# ATmega4809_Curiosity_Nano_Target_MCU.net
KiCad netlist of a schematic drawn in Altium Designer
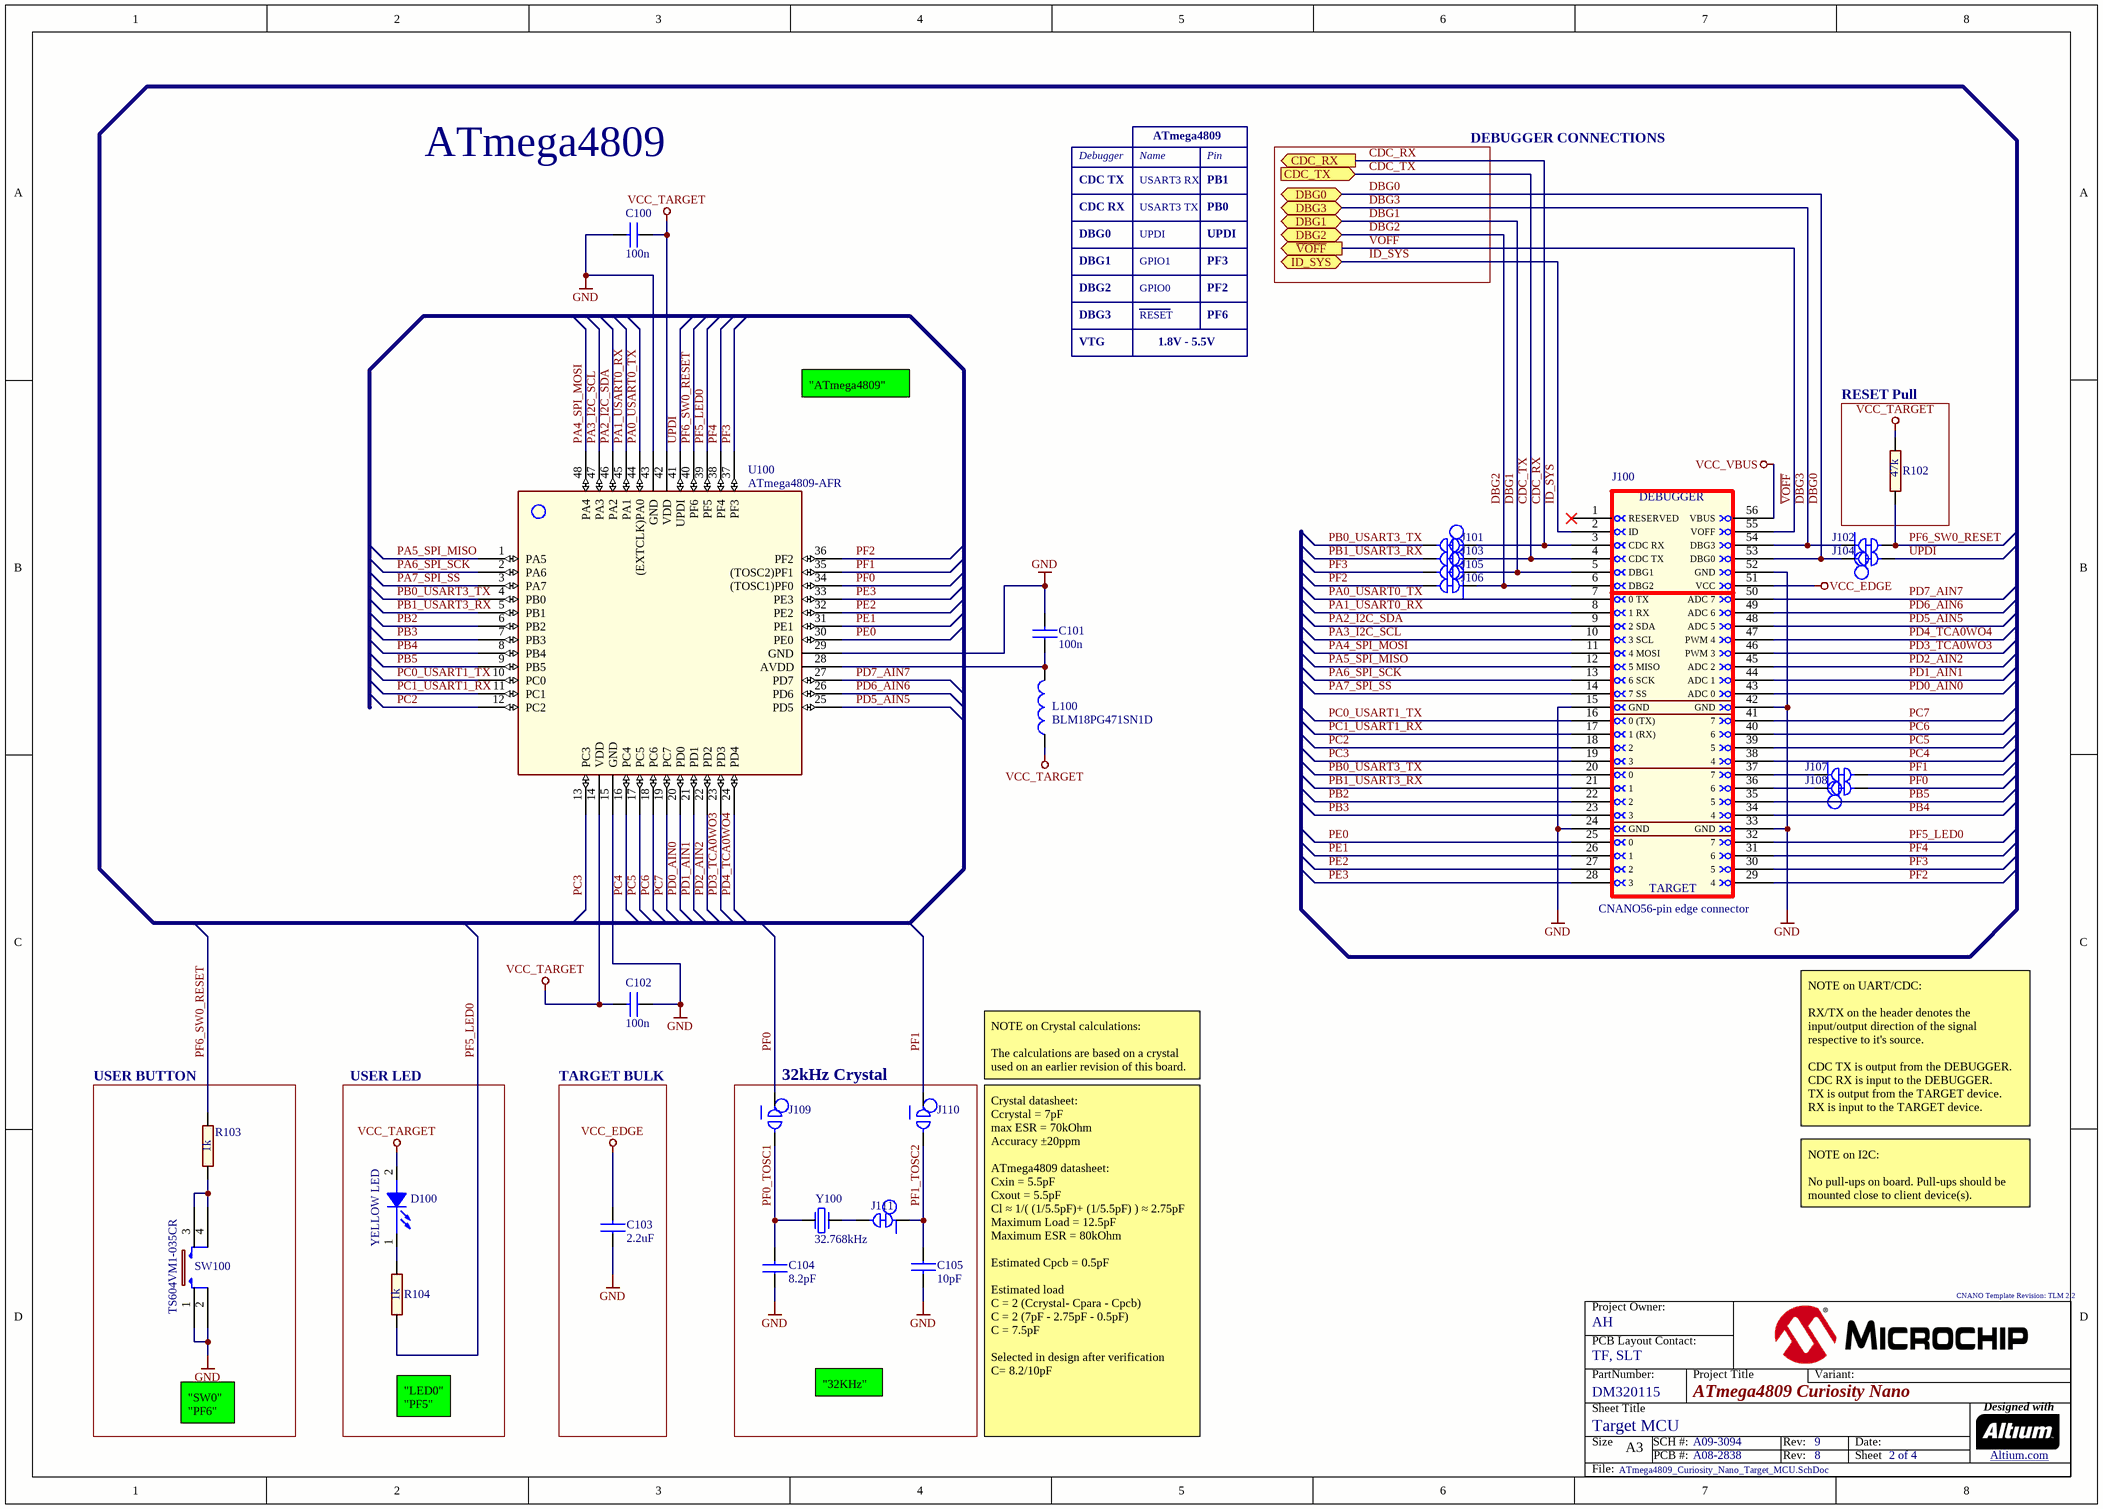
[diagram p0: ATmega4809_Curiosity_Nano_Target_MCU.SchDoc]

(export (version "E")
  (design (tool "Eeschema 10.0.6"))
  (components
    (comp (ref "C100")
      (value "100n")
      (footprint "AP1-00148")
      (description "Ceramic capacitor, SMD 0402, X7R, 16V, +/-10%")
      (fields (field (name "TOLERANCE") "16V, +/-10%") (field (name "MANUFACTURER") "Yageo"))
      (libsource (lib "AltiumDbLib") (part "CAP-NONPOL"))
    )
    (comp (ref "C101")
      (value "100n")
      (footprint "AP1-00148")
      (description "Ceramic capacitor, SMD 0402, X7R, 16V, +/-10%")
      (fields (field (name "TOLERANCE") "16V, +/-10%") (field (name "MANUFACTURER") "Yageo"))
      (libsource (lib "AltiumDbLib") (part "CAP-NONPOL"))
    )
    (comp (ref "C102")
      (value "100n")
      (footprint "AP1-00148")
      (description "Ceramic capacitor, SMD 0402, X7R, 16V, +/-10%")
      (fields (field (name "TOLERANCE") "16V, +/-10%") (field (name "MANUFACTURER") "Yageo"))
      (libsource (lib "AltiumDbLib") (part "CAP-NONPOL"))
    )
    (comp (ref "C103")
      (value "2.2uF")
      (footprint "AP1-00148")
      (description "CAP CER 2.2UF 10V 10% X5R 0402")
      (fields (field (name "TOLERANCE") "+/-10%") (field (name "MANUFACTURER") "TDK"))
      (libsource (lib "AltiumDbLib") (part "CAP-NONPOL"))
    )
    (comp (ref "C104")
      (value "8.2pF")
      (footprint "AP1-00141")
      (description "8.2pF GCQ15 Series HiQ Automotive 0402(EIA)")
      (fields (field (name "TOLERANCE") "+/-0.5") (field (name "MANUFACTURER") "Murata"))
      (libsource (lib "AltiumDbLib") (part "CAP-NONPOL"))
    )
    (comp (ref "C105")
      (value "10pF")
      (footprint "AP1-00038")
      (description "Ceramic capacitor, SMD 0402, NP0, 50V, +/-5% (de16674)")
      (fields (field (name "TOLERANCE") "5%") (field (name "MANUFACTURER") "Yageo"))
      (libsource (lib "AltiumDbLib") (part "CAP-NONPOL"))
    )
    (comp (ref "D100")
      (value "YELLOW LED")
      (footprint "AP4-00169")
      (description "LED, SMD 0603, Yellow, Wave length=590nm, 100mcd @ (20mA, 2.2Vf) rohm")
      (fields (field (name "MANUFACTURER") "ROHM") (field (name "MPN") "SML-D12Y1WT86"))
      (libsource (lib "AltiumDbLib") (part "LED_12"))
    )
    (comp (ref "J100")
      (value "CNANO56-pin edge connector")
      (footprint "AP8-01100")
      (description "Curiosity Nano 56-pin edge connector with castellations, 100-mil pitch.")
      (libsource (lib "AltiumDbLib") (part "CNANO_Connector_56"))
    )
    (comp (ref "J101")
      (value "~")
      (footprint "AP8-01166")
      (description "Closed Link 0402 w/50mil hole")
      (libsource (lib "AltiumDbLib") (part "SMD-STRAP_CLOSED"))
    )
    (comp (ref "J102")
      (value "~")
      (footprint "AP8-01166")
      (description "Closed Link 0402 w/50mil hole")
      (libsource (lib "AltiumDbLib") (part "SMD-STRAP_CLOSED"))
    )
    (comp (ref "J103")
      (value "~")
      (footprint "AP8-01166")
      (description "Closed Link 0402 w/50mil hole")
      (libsource (lib "AltiumDbLib") (part "SMD-STRAP_CLOSED"))
    )
    (comp (ref "J104")
      (value "~")
      (footprint "AP8-01166")
      (description "Closed Link 0402 w/50mil hole")
      (libsource (lib "AltiumDbLib") (part "SMD-STRAP_CLOSED"))
    )
    (comp (ref "J105")
      (value "~")
      (footprint "AP8-01166")
      (description "Closed Link 0402 w/50mil hole")
      (libsource (lib "AltiumDbLib") (part "SMD-STRAP_CLOSED"))
    )
    (comp (ref "J106")
      (value "~")
      (footprint "AP8-01166")
      (description "Closed Link 0402 w/50mil hole")
      (libsource (lib "AltiumDbLib") (part "SMD-STRAP_CLOSED"))
    )
    (comp (ref "J107")
      (value "~")
      (footprint "AP8-01166")
      (description "Closed Link 0402 w/50mil hole")
      (libsource (lib "AltiumDbLib") (part "SMD-STRAP_CLOSED"))
    )
    (comp (ref "J108")
      (value "~")
      (footprint "AP8-01166")
      (description "Closed Link 0402 w/50mil hole")
      (libsource (lib "AltiumDbLib") (part "SMD-STRAP_CLOSED"))
    )
    (comp (ref "J109")
      (value "~")
      (footprint "AP9-00172")
      (description "1x1mm, Round Strap, Open, no frame")
      (libsource (lib "AltiumDbLib") (part "SMD-STRAP_OPEN"))
    )
    (comp (ref "J110")
      (value "~")
      (footprint "AP9-00172")
      (description "1x1mm, Round Strap, Open, no frame")
      (libsource (lib "AltiumDbLib") (part "SMD-STRAP_OPEN"))
    )
    (comp (ref "J111")
      (value "~")
      (footprint "AP8-00595")
      (description "Closed Link 0402")
      (libsource (lib "AltiumDbLib") (part "SMD-STRAP_CLOSED"))
    )
    (comp (ref "L100")
      (value "BLM18PG471SN1D")
      (footprint "AP3-00005")
      (description "SMD RF inductor 0603. Z=470Ohm (@100MHz), Max R(dc)=0.20Ohm, Max current=1A")
      (fields
        (field (name "MANUFACTURER") "Murata")
        (field (name "Comment") "part number either has \"D\" (tape and reel) or \"B\" (Bulk) at the end.")
      )
      (libsource (lib "AltiumDbLib") (part "INDUCTOR"))
    )
    (comp (ref "R102")
      (value "47k")
      (footprint "AP2-00108")
      (description "Thick film resistor, SMD 0402, 1/16W, 1%")
      (fields (field (name "TOLERANCE") "1 %") (field (name "MANUFACTURER") "KOA"))
      (libsource (lib "AltiumDbLib") (part "R2"))
    )
    (comp (ref "R103")
      (value "1k")
      (footprint "AP2-00108")
      (description "Thick film resistor, SMD 0402, 1/16W, 1%")
      (fields (field (name "TOLERANCE") "1 %") (field (name "MANUFACTURER") "Yageo"))
      (libsource (lib "") (part "R2_1"))
    )
    (comp (ref "R104")
      (value "1k")
      (footprint "AP2-00108")
      (description "Thick film resistor, SMD 0402, 1/16W, 1%")
      (fields (field (name "TOLERANCE") "1 %") (field (name "MANUFACTURER") "Yageo"))
      (libsource (lib "AltiumDbLib") (part "R2"))
    )
    (comp (ref "SW100")
      (value "TS604VM1-035CR")
      (footprint "AP8-00137")
      (description "SWITCH, SMD, 260gf, 6.4mm X 6.2mm")
      (fields
        (field (name "MANUFACTURER") "Dailywell Electronics Co.LTD")
        (field (name "MPN") "TS604VM1-035CR-R")
      )
      (libsource (lib "AltiumDbLib") (part "PUSHBUTTON1"))
    )
    (comp (ref "U100")
      (value "ATmega4809-AFR")
      (footprint "AP6-00357")
      (description "Atmel 8-bit RISC MCU, 48K Flash, 48pin TQFP, 7x7mm, 0.5m pitch package")
      (fields (field (name "MANUFACTURER") "Microchip"))
      (libsource (lib "AltiumDbLib") (part "ATmega4809-AFRES"))
    )
    (comp (ref "Y100")
      (value "32.768kHz")
      (footprint "AP7-00069")
      (description "Crystal, 32.768kHz, CL=9.0pF, ESR=70kOhm, SMD  LxW=3.2 x 1.5mm, 20ppm")
      (fields (field (name "TOLERANCE") "20ppm") (field (name "MANUFACTURER") "Microchip"))
      (libsource (lib "AltiumDbLib") (part "CRYSTAL"))
    )
  )
  (nets
    (net (code "1") (name "/CDC_RX") (class "Default")
      (node (ref "J100") (pin "3") (pinfunction "CDC_RX_3") (pintype "passive"))
      (node (ref "J101") (pin "1") (pinfunction "1_1") (pintype "passive"))
    )
    (net (code "2") (name "/CDC_TX") (class "Default")
      (node (ref "J100") (pin "4") (pinfunction "CDC_TX_4") (pintype "passive"))
      (node (ref "J103") (pin "1") (pinfunction "1_1") (pintype "passive"))
    )
    (net (code "3") (name "/DBG0") (class "Default")
      (node (ref "J100") (pin "53") (pinfunction "DBG0_53") (pintype "passive"))
      (node (ref "J104") (pin "1") (pinfunction "1_1") (pintype "passive"))
    )
    (net (code "4") (name "/DBG1") (class "Default")
      (node (ref "J100") (pin "5") (pinfunction "DBG1_5") (pintype "passive"))
      (node (ref "J105") (pin "1") (pinfunction "1_1") (pintype "passive"))
    )
    (net (code "5") (name "/DBG2") (class "Default")
      (node (ref "J100") (pin "6") (pinfunction "DBG2_6") (pintype "passive"))
      (node (ref "J106") (pin "1") (pinfunction "1_1") (pintype "passive"))
    )
    (net (code "6") (name "/DBG3") (class "Default")
      (node (ref "J100") (pin "54") (pinfunction "DBG3_54") (pintype "passive"))
      (node (ref "J102") (pin "1") (pinfunction "1_1") (pintype "passive"))
    )
    (net (code "7") (name "/ID_SYS") (class "Default")
      (node (ref "J100") (pin "2") (pinfunction "ID_2") (pintype "passive"))
    )
    (net (code "8") (name "/PA0_USART0_TX") (class "Default")
      (node (ref "J100") (pin "7") (pinfunction "0_TX_7") (pintype "passive"))
      (node (ref "U100") (pin "44") (pinfunction "(EXTCLK)PA0_44") (pintype "bidirectional"))
    )
    (net (code "9") (name "/PA1_USART0_RX") (class "Default")
      (node (ref "J100") (pin "8") (pinfunction "1_RX_8") (pintype "passive"))
      (node (ref "U100") (pin "45") (pinfunction "PA1_45") (pintype "bidirectional"))
    )
    (net (code "10") (name "/PA2_I2C_SDA") (class "Default")
      (node (ref "J100") (pin "9") (pinfunction "2_SDA_9") (pintype "passive"))
      (node (ref "U100") (pin "46") (pinfunction "PA2_46") (pintype "bidirectional"))
    )
    (net (code "11") (name "/PA3_I2C_SCL") (class "Default")
      (node (ref "J100") (pin "10") (pinfunction "3_SCL_10") (pintype "passive"))
      (node (ref "U100") (pin "47") (pinfunction "PA3_47") (pintype "bidirectional"))
    )
    (net (code "12") (name "/PA4_SPI_MOSI") (class "Default")
      (node (ref "J100") (pin "11") (pinfunction "4_MOSI_11") (pintype "passive"))
      (node (ref "U100") (pin "48") (pinfunction "PA4_48") (pintype "bidirectional"))
    )
    (net (code "13") (name "/PA5_SPI_MISO") (class "Default")
      (node (ref "J100") (pin "12") (pinfunction "5_MISO_12") (pintype "passive"))
      (node (ref "U100") (pin "1") (pinfunction "PA5_1") (pintype "bidirectional"))
    )
    (net (code "14") (name "/PA6_SPI_SCK") (class "Default")
      (node (ref "J100") (pin "13") (pinfunction "6_SCK_13") (pintype "passive"))
      (node (ref "U100") (pin "2") (pinfunction "PA6_2") (pintype "bidirectional"))
    )
    (net (code "15") (name "/PA7_SPI_SS") (class "Default")
      (node (ref "J100") (pin "14") (pinfunction "7_SS_14") (pintype "passive"))
      (node (ref "U100") (pin "3") (pinfunction "PA7_3") (pintype "bidirectional"))
    )
    (net (code "16") (name "/PB0_USART3_TX") (class "Default")
      (node (ref "J100") (pin "20") (pinfunction "0_20") (pintype "passive"))
      (node (ref "J101") (pin "2") (pinfunction "2_2") (pintype "passive"))
      (node (ref "U100") (pin "4") (pinfunction "PB0_4") (pintype "bidirectional"))
    )
    (net (code "17") (name "/PB1_USART3_RX") (class "Default")
      (node (ref "J100") (pin "21") (pinfunction "1_21") (pintype "passive"))
      (node (ref "J103") (pin "2") (pinfunction "2_2") (pintype "passive"))
      (node (ref "U100") (pin "5") (pinfunction "PB1_5") (pintype "bidirectional"))
    )
    (net (code "18") (name "/PB2") (class "Default")
      (node (ref "J100") (pin "22") (pinfunction "2_22") (pintype "passive"))
      (node (ref "U100") (pin "6") (pinfunction "PB2_6") (pintype "bidirectional"))
    )
    (net (code "19") (name "/PB3") (class "Default")
      (node (ref "J100") (pin "23") (pinfunction "3_23") (pintype "passive"))
      (node (ref "U100") (pin "7") (pinfunction "PB3_7") (pintype "bidirectional"))
    )
    (net (code "20") (name "/PB4") (class "Default")
      (node (ref "J100") (pin "34") (pinfunction "4_34") (pintype "passive"))
      (node (ref "U100") (pin "8") (pinfunction "PB4_8") (pintype "bidirectional"))
    )
    (net (code "21") (name "/PB5") (class "Default")
      (node (ref "J100") (pin "35") (pinfunction "5_35") (pintype "passive"))
      (node (ref "U100") (pin "9") (pinfunction "PB5_9") (pintype "bidirectional"))
    )
    (net (code "22") (name "/PC0_USART1_TX") (class "Default")
      (node (ref "J100") (pin "16") (pinfunction "0_(TX)_16") (pintype "passive"))
      (node (ref "U100") (pin "10") (pinfunction "PC0_10") (pintype "bidirectional"))
    )
    (net (code "23") (name "/PC1_USART1_RX") (class "Default")
      (node (ref "J100") (pin "17") (pinfunction "1_(RX)_17") (pintype "passive"))
      (node (ref "U100") (pin "11") (pinfunction "PC1_11") (pintype "bidirectional"))
    )
    (net (code "24") (name "/PC2") (class "Default")
      (node (ref "J100") (pin "18") (pinfunction "2_18") (pintype "passive"))
      (node (ref "U100") (pin "12") (pinfunction "PC2_12") (pintype "bidirectional"))
    )
    (net (code "25") (name "/PC3") (class "Default")
      (node (ref "J100") (pin "19") (pinfunction "3_19") (pintype "passive"))
      (node (ref "U100") (pin "13") (pinfunction "PC3_13") (pintype "bidirectional"))
    )
    (net (code "26") (name "/PC4") (class "Default")
      (node (ref "J100") (pin "38") (pinfunction "4_38") (pintype "passive"))
      (node (ref "U100") (pin "16") (pinfunction "PC4_16") (pintype "bidirectional"))
    )
    (net (code "27") (name "/PC5") (class "Default")
      (node (ref "J100") (pin "39") (pinfunction "5_39") (pintype "passive"))
      (node (ref "U100") (pin "17") (pinfunction "PC5_17") (pintype "bidirectional"))
    )
    (net (code "28") (name "/PC6") (class "Default")
      (node (ref "J100") (pin "40") (pinfunction "6_40") (pintype "passive"))
      (node (ref "U100") (pin "18") (pinfunction "PC6_18") (pintype "bidirectional"))
    )
    (net (code "29") (name "/PC7") (class "Default")
      (node (ref "J100") (pin "41") (pinfunction "7_41") (pintype "passive"))
      (node (ref "U100") (pin "19") (pinfunction "PC7_19") (pintype "bidirectional"))
    )
    (net (code "30") (name "/PD0_AIN0") (class "Default")
      (node (ref "J100") (pin "43") (pinfunction "ADC_0_43") (pintype "passive"))
      (node (ref "U100") (pin "20") (pinfunction "PD0_20") (pintype "bidirectional"))
    )
    (net (code "31") (name "/PD1_AIN1") (class "Default")
      (node (ref "J100") (pin "44") (pinfunction "ADC_1_44") (pintype "passive"))
      (node (ref "U100") (pin "21") (pinfunction "PD1_21") (pintype "bidirectional"))
    )
    (net (code "32") (name "/PD2_AIN2") (class "Default")
      (node (ref "J100") (pin "45") (pinfunction "ADC_2_45") (pintype "passive"))
      (node (ref "U100") (pin "22") (pinfunction "PD2_22") (pintype "bidirectional"))
    )
    (net (code "33") (name "/PD3_TCA0WO3") (class "Default")
      (node (ref "J100") (pin "46") (pinfunction "PWM_3_46") (pintype "passive"))
      (node (ref "U100") (pin "23") (pinfunction "PD3_23") (pintype "bidirectional"))
    )
    (net (code "34") (name "/PD4_TCA0WO4") (class "Default")
      (node (ref "J100") (pin "47") (pinfunction "PWM_4_47") (pintype "passive"))
      (node (ref "U100") (pin "24") (pinfunction "PD4_24") (pintype "bidirectional"))
    )
    (net (code "35") (name "/PD5_AIN5") (class "Default")
      (node (ref "J100") (pin "48") (pinfunction "ADC_5_48") (pintype "passive"))
      (node (ref "U100") (pin "25") (pinfunction "PD5_25") (pintype "bidirectional"))
    )
    (net (code "36") (name "/PD6_AIN6") (class "Default")
      (node (ref "J100") (pin "49") (pinfunction "ADC_6_49") (pintype "passive"))
      (node (ref "U100") (pin "26") (pinfunction "PD6_26") (pintype "bidirectional"))
    )
    (net (code "37") (name "/PD7_AIN7") (class "Default")
      (node (ref "J100") (pin "50") (pinfunction "ADC_7_50") (pintype "passive"))
      (node (ref "U100") (pin "27") (pinfunction "PD7_27") (pintype "bidirectional"))
    )
    (net (code "38") (name "/PE0") (class "Default")
      (node (ref "J100") (pin "25") (pinfunction "0_25") (pintype "passive"))
      (node (ref "U100") (pin "30") (pinfunction "PE0_30") (pintype "bidirectional"))
    )
    (net (code "39") (name "/PE1") (class "Default")
      (node (ref "J100") (pin "26") (pinfunction "1_26") (pintype "passive"))
      (node (ref "U100") (pin "31") (pinfunction "PE1_31") (pintype "bidirectional"))
    )
    (net (code "40") (name "/PE2") (class "Default")
      (node (ref "J100") (pin "27") (pinfunction "2_27") (pintype "passive"))
      (node (ref "U100") (pin "32") (pinfunction "PE2_32") (pintype "bidirectional"))
    )
    (net (code "41") (name "/PE3") (class "Default")
      (node (ref "J100") (pin "28") (pinfunction "3_28") (pintype "passive"))
      (node (ref "U100") (pin "33") (pinfunction "PE3_33") (pintype "bidirectional"))
    )
    (net (code "42") (name "/PF0") (class "Default")
      (node (ref "J108") (pin "2") (pinfunction "2_2") (pintype "passive"))
      (node (ref "J109") (pin "1") (pinfunction "1_1") (pintype "passive"))
      (node (ref "U100") (pin "34") (pinfunction "(TOSC1)PF0_34") (pintype "bidirectional"))
    )
    (net (code "43") (name "/PF0_TOSC1") (class "Default")
      (node (ref "C104") (pin "2") (pinfunction "2_2") (pintype "passive"))
      (node (ref "J109") (pin "2") (pinfunction "2_2") (pintype "passive"))
      (node (ref "Y100") (pin "1") (pinfunction "1_1") (pintype "passive"))
    )
    (net (code "44") (name "/PF1") (class "Default")
      (node (ref "J107") (pin "2") (pinfunction "2_2") (pintype "passive"))
      (node (ref "J110") (pin "1") (pinfunction "1_1") (pintype "passive"))
      (node (ref "U100") (pin "35") (pinfunction "(TOSC2)PF1_35") (pintype "bidirectional"))
    )
    (net (code "45") (name "/PF1_TOSC2") (class "Default")
      (node (ref "C105") (pin "1") (pinfunction "1_1") (pintype "passive"))
      (node (ref "J110") (pin "2") (pinfunction "2_2") (pintype "passive"))
      (node (ref "J111") (pin "1") (pinfunction "1_1") (pintype "passive"))
    )
    (net (code "46") (name "/PF2") (class "Default")
      (node (ref "J100") (pin "29") (pinfunction "4_29") (pintype "passive"))
      (node (ref "J106") (pin "2") (pinfunction "2_2") (pintype "passive"))
      (node (ref "U100") (pin "36") (pinfunction "PF2_36") (pintype "bidirectional"))
    )
    (net (code "47") (name "/PF3") (class "Default")
      (node (ref "J100") (pin "30") (pinfunction "5_30") (pintype "passive"))
      (node (ref "J105") (pin "2") (pinfunction "2_2") (pintype "passive"))
      (node (ref "U100") (pin "37") (pinfunction "PF3_37") (pintype "bidirectional"))
    )
    (net (code "48") (name "/PF4") (class "Default")
      (node (ref "J100") (pin "31") (pinfunction "6_31") (pintype "passive"))
      (node (ref "U100") (pin "38") (pinfunction "PF4_38") (pintype "bidirectional"))
    )
    (net (code "49") (name "/PF5_LED0") (class "Default")
      (node (ref "J100") (pin "32") (pinfunction "7_32") (pintype "passive"))
      (node (ref "R104") (pin "1") (pinfunction "1_1") (pintype "passive"))
      (node (ref "U100") (pin "39") (pinfunction "PF5_39") (pintype "bidirectional"))
    )
    (net (code "50") (name "/PF6_SW0_RESET") (class "Default")
      (node (ref "J102") (pin "2") (pinfunction "2_2") (pintype "passive"))
      (node (ref "R102") (pin "1") (pinfunction "1_1") (pintype "passive"))
      (node (ref "R103") (pin "1") (pinfunction "1_1") (pintype "passive"))
      (node (ref "U100") (pin "40") (pinfunction "PF6_40") (pintype "bidirectional"))
    )
    (net (code "51") (name "/UPDI") (class "Default")
      (node (ref "J104") (pin "2") (pinfunction "2_2") (pintype "passive"))
      (node (ref "U100") (pin "41") (pinfunction "UPDI_41") (pintype "bidirectional"))
    )
    (net (code "52") (name "/~{VOFF}") (class "Default")
      (node (ref "J100") (pin "55") (pinfunction "VOFF_55") (pintype "passive"))
    )
    (net (code "53") (name "GND") (class "Default")
      (node (ref "C100") (pin "2") (pinfunction "2_2") (pintype "passive"))
      (node (ref "C101") (pin "2") (pinfunction "2_2") (pintype "passive"))
      (node (ref "C102") (pin "1") (pinfunction "1_1") (pintype "passive"))
      (node (ref "C103") (pin "1") (pinfunction "1_1") (pintype "passive"))
      (node (ref "C104") (pin "1") (pinfunction "1_1") (pintype "passive"))
      (node (ref "C105") (pin "2") (pinfunction "2_2") (pintype "passive"))
      (node (ref "J100") (pin "15") (pinfunction "GND_15") (pintype "power_in"))
      (node (ref "J100") (pin "24") (pinfunction "GND_24") (pintype "power_in"))
      (node (ref "J100") (pin "33") (pinfunction "GND_33") (pintype "power_in"))
      (node (ref "J100") (pin "42") (pinfunction "GND_42") (pintype "power_in"))
      (node (ref "J100") (pin "52") (pinfunction "GND_52") (pintype "power_in"))
      (node (ref "SW100") (pin "1") (pinfunction "1_1") (pintype "passive"))
      (node (ref "SW100") (pin "2") (pinfunction "2_2") (pintype "passive"))
      (node (ref "U100") (pin "15") (pinfunction "GND_15") (pintype "power_in"))
      (node (ref "U100") (pin "29") (pinfunction "GND_29") (pintype "power_in"))
      (node (ref "U100") (pin "43") (pinfunction "GND_43") (pintype "power_in"))
    )
    (net (code "54") (name "Net-(D100-CATHODE)") (class "Default")
      (node (ref "D100") (pin "1") (pinfunction "CATHODE_1") (pintype "passive"))
      (node (ref "R104") (pin "2") (pinfunction "2_2") (pintype "passive"))
    )
    (net (code "55") (name "Net-(J100-6-Pad36)") (class "Default")
      (node (ref "J100") (pin "36") (pinfunction "6_36") (pintype "passive"))
      (node (ref "J108") (pin "1") (pinfunction "1_1") (pintype "passive"))
    )
    (net (code "56") (name "Net-(J100-7-Pad37)") (class "Default")
      (node (ref "J100") (pin "37") (pinfunction "7_37") (pintype "passive"))
      (node (ref "J107") (pin "1") (pinfunction "1_1") (pintype "passive"))
    )
    (net (code "57") (name "Net-(J111-Pad2)") (class "Default")
      (node (ref "J111") (pin "2") (pinfunction "2_2") (pintype "passive"))
      (node (ref "Y100") (pin "2") (pinfunction "2_2") (pintype "passive"))
    )
    (net (code "58") (name "Net-(R103-Pad2)") (class "Default")
      (node (ref "R103") (pin "2") (pinfunction "2_2") (pintype "passive"))
      (node (ref "SW100") (pin "3") (pinfunction "3_3") (pintype "passive"))
      (node (ref "SW100") (pin "4") (pinfunction "4_4") (pintype "passive"))
    )
    (net (code "59") (name "Net-(U100-AVDD)") (class "Default")
      (node (ref "C101") (pin "1") (pinfunction "1_1") (pintype "passive"))
      (node (ref "L100") (pin "2") (pinfunction "2_2") (pintype "passive"))
      (node (ref "U100") (pin "28") (pinfunction "AVDD_28") (pintype "power_in"))
    )
    (net (code "60") (name "VCC_EDGE") (class "Default")
      (node (ref "C103") (pin "2") (pinfunction "2_2") (pintype "passive"))
      (node (ref "J100") (pin "51") (pinfunction "VCC_51") (pintype "power_in"))
    )
    (net (code "61") (name "VCC_TARGET") (class "Default")
      (node (ref "C100") (pin "1") (pinfunction "1_1") (pintype "passive"))
      (node (ref "C102") (pin "2") (pinfunction "2_2") (pintype "passive"))
      (node (ref "D100") (pin "2") (pinfunction "ANODE_2") (pintype "passive"))
      (node (ref "L100") (pin "1") (pinfunction "1_1") (pintype "passive"))
      (node (ref "R102") (pin "2") (pinfunction "2_2") (pintype "passive"))
      (node (ref "U100") (pin "14") (pinfunction "VDD_14") (pintype "power_in"))
      (node (ref "U100") (pin "42") (pinfunction "VDD_42") (pintype "power_in"))
    )
    (net (code "62") (name "VCC_VBUS") (class "Default")
      (node (ref "J100") (pin "56") (pinfunction "VBUS_56") (pintype "passive"))
    )
    (net (code "63") (name "unconnected-(J100-RESERVED-Pad1)") (class "Default")
      (node (ref "J100") (pin "1") (pinfunction "RESERVED_1") (pintype "passive+no_connect"))
    )
  )
)
